# DashHubV6.net
KiCad netlist of a schematic drawn in EAGLE
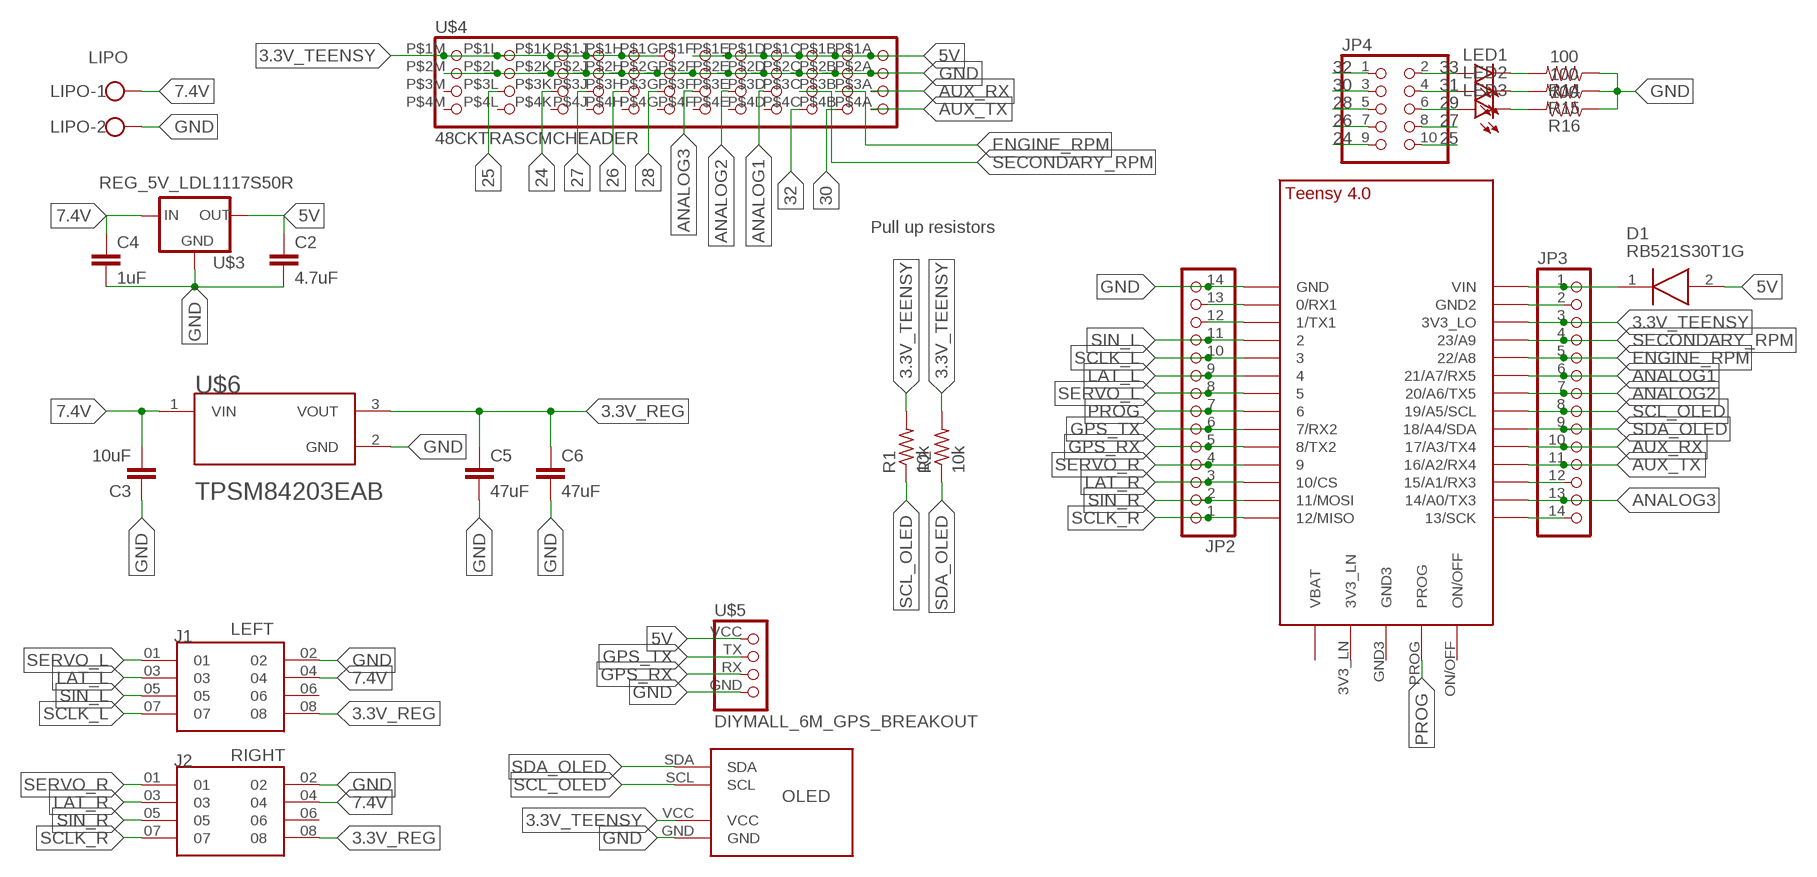
[diagram p0: schematic, sheet 1]

(export (version "E")
  (design (tool "Eeschema 10.0.6"))
  (components
    (comp (ref "C2")
      (value "4.7uF")
      (footprint "eagle-import:C0603")
      (libsource (lib "eagle-import") (part "CAP_SMDC0603"))
    )
    (comp (ref "C3")
      (value "10uF")
      (footprint "eagle-import:C1206")
      (libsource (lib "eagle-import") (part "CAP_SMDC1206"))
    )
    (comp (ref "C4")
      (value "1uF")
      (footprint "eagle-import:C1206")
      (libsource (lib "eagle-import") (part "CAP_SMDC1206"))
    )
    (comp (ref "C5")
      (value "47uF")
      (footprint "eagle-import:C1206")
      (libsource (lib "eagle-import") (part "CAP_SMDC1206"))
    )
    (comp (ref "C6")
      (value "47uF")
      (footprint "eagle-import:C1206")
      (libsource (lib "eagle-import") (part "CAP_SMDC1206"))
    )
    (comp (ref "D1")
      (value "RB521S30T1G")
      (footprint "eagle-import:SODFL1608X70N")
      (fields (field (name "MOUSER_PART_NUMBER") "863-RB521S30T1G"))
      (libsource (lib "eagle-import") (part "RB521S30T1G"))
    )
    (comp (ref "J1")
      (value "LEFT")
      (footprint "eagle-import:SAMTEC_ESW-104-23-L-D")
      (fields (field (name "MANUFACTURER") "Samtec Inc."))
      (libsource (lib "eagle-import") (part "ESW-104-23-L-D"))
    )
    (comp (ref "J2")
      (value "RIGHT")
      (footprint "eagle-import:SAMTEC_ESW-104-23-L-D")
      (fields (field (name "MANUFACTURER") "Samtec Inc."))
      (libsource (lib "eagle-import") (part "ESW-104-23-L-D"))
    )
    (comp (ref "JP2")
      (value "PINHD-1X14")
      (footprint "eagle-import:1X14")
      (libsource (lib "eagle-import") (part "PINHD-1X14"))
    )
    (comp (ref "JP3")
      (value "PINHD-1X14")
      (footprint "eagle-import:1X14")
      (libsource (lib "eagle-import") (part "PINHD-1X14"))
    )
    (comp (ref "JP4")
      (value "PINHD-2X5")
      (footprint "eagle-import:2X05")
      (libsource (lib "eagle-import") (part "PINHD-2X5"))
    )
    (comp (ref "LED1")
      (value "LEDCHIPLED_1206")
      (footprint "eagle-import:CHIPLED_1206")
      (libsource (lib "eagle-import") (part "LEDCHIPLED_1206"))
    )
    (comp (ref "LED2")
      (value "LEDCHIPLED_1206")
      (footprint "eagle-import:CHIPLED_1206")
      (libsource (lib "eagle-import") (part "LEDCHIPLED_1206"))
    )
    (comp (ref "LED3")
      (value "LEDCHIPLED_1206")
      (footprint "eagle-import:CHIPLED_1206")
      (libsource (lib "eagle-import") (part "LEDCHIPLED_1206"))
    )
    (comp (ref "LIPO")
      (value "LIPO")
      (footprint "eagle-import:W237-102")
      (fields (field (name "MPN") "237-102"))
      (libsource (lib "eagle-import") (part "W237-102"))
    )
    (comp (ref "R1")
      (value "10k")
      (footprint "eagle-import:R0603")
      (libsource (lib "eagle-import") (part "RES_SMDR0603"))
    )
    (comp (ref "R2")
      (value "10k")
      (footprint "eagle-import:R0603")
      (libsource (lib "eagle-import") (part "RES_SMDR0603"))
    )
    (comp (ref "R14")
      (value "100")
      (footprint "eagle-import:AXIAL-0.3")
      (libsource (lib "eagle-import") (part "RESISTORAXIAL-0.3"))
    )
    (comp (ref "R15")
      (value "100")
      (footprint "eagle-import:AXIAL-0.3")
      (libsource (lib "eagle-import") (part "RESISTORAXIAL-0.3"))
    )
    (comp (ref "R16")
      (value "100")
      (footprint "eagle-import:AXIAL-0.3")
      (libsource (lib "eagle-import") (part "RESISTORAXIAL-0.3"))
    )
    (comp (ref "U$1")
      (value "TEENSY_4.0-BASIC")
      (footprint "eagle-import:TEENSY_4.0-BASIC")
      (libsource (lib "eagle-import") (part "TEENSY_4.0-BASIC"))
    )
    (comp (ref "U$2")
      (value "OLED_SSD1306")
      (footprint "eagle-import:OLED_SSD1306")
      (libsource (lib "eagle-import") (part "OLED_SSD1306"))
    )
    (comp (ref "U$3")
      (value "REG_5V_LDL1117S50R")
      (footprint "eagle-import:SOT230P700X180-4N")
      (libsource (lib "eagle-import") (part "REG_5V_LDL1117S50R"))
    )
    (comp (ref "U$4")
      (value "48CKTRASCMCHEADER")
      (footprint "eagle-import:48CKTRASCMCHEADER")
      (libsource (lib "eagle-import") (part "48CKTRASCMCHEADER"))
    )
    (comp (ref "U$5")
      (value "DIYMALL_6M_GPS_BREAKOUT")
      (footprint "eagle-import:DIYMALL_6M_GPS_BREAKOUT")
      (libsource (lib "eagle-import") (part "DIYMALL_6M_GPS_BREAKOUT"))
    )
    (comp (ref "U$6")
      (value "TPSM84205EAB")
      (footprint "eagle-import:TPSM84205EAB")
      (libsource (lib "eagle-import") (part "TPSM84205EAB"))
    )
  )
  (nets
    (net (code "1") (name "/29") (class "Default")
      (node (ref "JP4") (pin "6") (pinfunction "6_6") (pintype "passive"))
      (node (ref "LED3") (pin "A") (pinfunction "A_A") (pintype "passive"))
    )
    (net (code "2") (name "/31") (class "Default")
      (node (ref "JP4") (pin "4") (pinfunction "4_4") (pintype "passive"))
      (node (ref "LED2") (pin "A") (pinfunction "A_A") (pintype "passive"))
    )
    (net (code "3") (name "/33") (class "Default")
      (node (ref "JP4") (pin "2") (pinfunction "2_2") (pintype "passive"))
      (node (ref "LED1") (pin "A") (pinfunction "A_A") (pintype "passive"))
    )
    (net (code "4") (name "3.3V_REG") (class "Default")
      (node (ref "C5") (pin "1") (pinfunction "1_1") (pintype "passive"))
      (node (ref "C6") (pin "1") (pinfunction "1_1") (pintype "passive"))
      (node (ref "J1") (pin "08") (pinfunction "08_08") (pintype "passive"))
      (node (ref "J2") (pin "08") (pinfunction "08_08") (pintype "passive"))
      (node (ref "U$6") (pin "3") (pinfunction "VOUT_3") (pintype "power_in"))
    )
    (net (code "5") (name "3.3V_TEENSY") (class "Default")
      (node (ref "JP3") (pin "3") (pinfunction "3_3") (pintype "passive"))
      (node (ref "R1") (pin "2") (pinfunction "2_2") (pintype "passive"))
      (node (ref "R2") (pin "2") (pinfunction "2_2") (pintype "passive"))
      (node (ref "U$1") (pin "3V3_LO") (pinfunction "3V3_LO_3V3_LO") (pintype "bidirectional"))
      (node (ref "U$2") (pin "VCC") (pinfunction "VCC_VCC") (pintype "bidirectional"))
      (node (ref "U$4") (pin "P$1G") (pinfunction "1G_P$1G") (pintype "passive"))
      (node (ref "U$4") (pin "P$1H") (pinfunction "1H_P$1H") (pintype "passive"))
      (node (ref "U$4") (pin "P$1J") (pinfunction "1J_P$1J") (pintype "passive"))
      (node (ref "U$4") (pin "P$1K") (pinfunction "1K_P$1K") (pintype "passive"))
      (node (ref "U$4") (pin "P$1L") (pinfunction "1L_P$1L") (pintype "passive"))
      (node (ref "U$4") (pin "P$1M") (pinfunction "1M_P$1M") (pintype "passive"))
    )
    (net (code "6") (name "5V") (class "Default")
      (node (ref "C2") (pin "1") (pinfunction "1_1") (pintype "passive"))
      (node (ref "D1") (pin "2") (pinfunction "A_2") (pintype "bidirectional"))
      (node (ref "U$3") (pin "2") (pinfunction "OUT_2") (pintype "output"))
      (node (ref "U$3") (pin "4") (pinfunction "OUT_4") (pintype "output"))
      (node (ref "U$4") (pin "P$1A") (pinfunction "1A_P$1A") (pintype "passive"))
      (node (ref "U$4") (pin "P$1B") (pinfunction "1B_P$1B") (pintype "passive"))
      (node (ref "U$4") (pin "P$1C") (pinfunction "1C_P$1C") (pintype "passive"))
      (node (ref "U$4") (pin "P$1D") (pinfunction "1D_P$1D") (pintype "passive"))
      (node (ref "U$4") (pin "P$1E") (pinfunction "1E_P$1E") (pintype "passive"))
      (node (ref "U$4") (pin "P$1F") (pinfunction "1F_P$1F") (pintype "passive"))
      (node (ref "U$5") (pin "VCC") (pinfunction "VCC_VCC") (pintype "passive"))
    )
    (net (code "7") (name "7.4V") (class "Default")
      (node (ref "C3") (pin "2") (pinfunction "2_2") (pintype "passive"))
      (node (ref "C4") (pin "1") (pinfunction "1_1") (pintype "passive"))
      (node (ref "J1") (pin "04") (pinfunction "04_04") (pintype "passive"))
      (node (ref "J2") (pin "04") (pinfunction "04_04") (pintype "passive"))
      (node (ref "LIPO") (pin "1") (pinfunction "KL_1") (pintype "passive"))
      (node (ref "U$3") (pin "3") (pinfunction "IN_3") (pintype "input"))
      (node (ref "U$6") (pin "1") (pinfunction "VIN_1") (pintype "power_in"))
    )
    (net (code "8") (name "24") (class "Default")
      (node (ref "JP4") (pin "9") (pinfunction "9_9") (pintype "passive"))
      (node (ref "U$4") (pin "P$3K") (pinfunction "3K_P$3K") (pintype "passive"))
    )
    (net (code "9") (name "25") (class "Default")
      (node (ref "JP4") (pin "10") (pinfunction "10_10") (pintype "passive"))
      (node (ref "U$4") (pin "P$3L") (pinfunction "3L_P$3L") (pintype "passive"))
    )
    (net (code "10") (name "26") (class "Default")
      (node (ref "JP4") (pin "7") (pinfunction "7_7") (pintype "passive"))
      (node (ref "U$4") (pin "P$3H") (pinfunction "3H_P$3H") (pintype "passive"))
    )
    (net (code "11") (name "27") (class "Default")
      (node (ref "JP4") (pin "8") (pinfunction "8_8") (pintype "passive"))
      (node (ref "U$4") (pin "P$3J") (pinfunction "3J_P$3J") (pintype "passive"))
    )
    (net (code "12") (name "28") (class "Default")
      (node (ref "JP4") (pin "5") (pinfunction "5_5") (pintype "passive"))
      (node (ref "U$4") (pin "P$3G") (pinfunction "3G_P$3G") (pintype "passive"))
    )
    (net (code "13") (name "30") (class "Default")
      (node (ref "JP4") (pin "3") (pinfunction "3_3") (pintype "passive"))
      (node (ref "U$4") (pin "P$4B") (pinfunction "4B_P$4B") (pintype "passive"))
    )
    (net (code "14") (name "32") (class "Default")
      (node (ref "JP4") (pin "1") (pinfunction "1_1") (pintype "passive"))
      (node (ref "U$4") (pin "P$4C") (pinfunction "4C_P$4C") (pintype "passive"))
    )
    (net (code "15") (name "ANALOG1") (class "Default")
      (node (ref "JP3") (pin "6") (pinfunction "6_6") (pintype "passive"))
      (node (ref "U$1") (pin "21/A7") (pinfunction "21/A7/RX5_21/A7") (pintype "bidirectional"))
      (node (ref "U$4") (pin "P$3D") (pinfunction "3D_P$3D") (pintype "passive"))
    )
    (net (code "16") (name "ANALOG2") (class "Default")
      (node (ref "JP3") (pin "7") (pinfunction "7_7") (pintype "passive"))
      (node (ref "U$1") (pin "20/A6") (pinfunction "20/A6/TX5_20/A6") (pintype "bidirectional"))
      (node (ref "U$4") (pin "P$3E") (pinfunction "3E_P$3E") (pintype "passive"))
    )
    (net (code "17") (name "ANALOG3") (class "Default")
      (node (ref "JP3") (pin "13") (pinfunction "13_13") (pintype "passive"))
      (node (ref "U$1") (pin "14/A0") (pinfunction "14/A0/TX3_14/A0") (pintype "bidirectional"))
      (node (ref "U$4") (pin "P$3F") (pinfunction "3F_P$3F") (pintype "passive"))
    )
    (net (code "18") (name "AUX_RX") (class "Default")
      (node (ref "JP3") (pin "10") (pinfunction "10_10") (pintype "passive"))
      (node (ref "U$1") (pin "17/A3") (pinfunction "17/A3/TX4_17/A3") (pintype "bidirectional"))
      (node (ref "U$4") (pin "P$3A") (pinfunction "3A_P$3A") (pintype "passive"))
    )
    (net (code "19") (name "AUX_TX") (class "Default")
      (node (ref "JP3") (pin "11") (pinfunction "11_11") (pintype "passive"))
      (node (ref "U$1") (pin "16/A2") (pinfunction "16/A2/RX4_16/A2") (pintype "bidirectional"))
      (node (ref "U$4") (pin "P$4A") (pinfunction "4A_P$4A") (pintype "passive"))
    )
    (net (code "20") (name "ENGINE_RPM") (class "Default")
      (node (ref "JP3") (pin "5") (pinfunction "5_5") (pintype "passive"))
      (node (ref "U$1") (pin "22/A8") (pinfunction "22/A8_22/A8") (pintype "bidirectional"))
      (node (ref "U$4") (pin "P$3B") (pinfunction "3B_P$3B") (pintype "passive"))
    )
    (net (code "21") (name "GND") (class "Default")
      (node (ref "C2") (pin "2") (pinfunction "2_2") (pintype "passive"))
      (node (ref "C3") (pin "1") (pinfunction "1_1") (pintype "passive"))
      (node (ref "C4") (pin "2") (pinfunction "2_2") (pintype "passive"))
      (node (ref "C5") (pin "2") (pinfunction "2_2") (pintype "passive"))
      (node (ref "C6") (pin "2") (pinfunction "2_2") (pintype "passive"))
      (node (ref "J1") (pin "02") (pinfunction "02_02") (pintype "passive"))
      (node (ref "J2") (pin "02") (pinfunction "02_02") (pintype "passive"))
      (node (ref "JP2") (pin "14") (pinfunction "14_14") (pintype "passive"))
      (node (ref "LIPO") (pin "2") (pinfunction "KL_2") (pintype "passive"))
      (node (ref "R14") (pin "P$1") (pinfunction "1_P$1") (pintype "passive"))
      (node (ref "R15") (pin "P$1") (pinfunction "1_P$1") (pintype "passive"))
      (node (ref "R16") (pin "P$1") (pinfunction "1_P$1") (pintype "passive"))
      (node (ref "U$1") (pin "GND") (pinfunction "GND_GND") (pintype "bidirectional"))
      (node (ref "U$2") (pin "GND") (pinfunction "GND_GND") (pintype "bidirectional"))
      (node (ref "U$3") (pin "1") (pinfunction "GND_1") (pintype "input"))
      (node (ref "U$4") (pin "P$2A") (pinfunction "2A_P$2A") (pintype "passive"))
      (node (ref "U$4") (pin "P$2B") (pinfunction "2B_P$2B") (pintype "passive"))
      (node (ref "U$4") (pin "P$2C") (pinfunction "2C_P$2C") (pintype "passive"))
      (node (ref "U$4") (pin "P$2D") (pinfunction "2D_P$2D") (pintype "passive"))
      (node (ref "U$4") (pin "P$2E") (pinfunction "2E_P$2E") (pintype "passive"))
      (node (ref "U$4") (pin "P$2F") (pinfunction "2F_P$2F") (pintype "passive"))
      (node (ref "U$4") (pin "P$2G") (pinfunction "2G_P$2G") (pintype "passive"))
      (node (ref "U$4") (pin "P$2H") (pinfunction "2H_P$2H") (pintype "passive"))
      (node (ref "U$4") (pin "P$2J") (pinfunction "2J_P$2J") (pintype "passive"))
      (node (ref "U$4") (pin "P$2K") (pinfunction "2K_P$2K") (pintype "passive"))
      (node (ref "U$4") (pin "P$2L") (pinfunction "2L_P$2L") (pintype "passive"))
      (node (ref "U$4") (pin "P$2M") (pinfunction "2M_P$2M") (pintype "passive"))
      (node (ref "U$5") (pin "GND") (pinfunction "GND_GND") (pintype "passive"))
      (node (ref "U$6") (pin "2") (pinfunction "GND_2") (pintype "power_in"))
    )
    (net (code "22") (name "GPS_RX") (class "Default")
      (node (ref "JP2") (pin "5") (pinfunction "5_5") (pintype "passive"))
      (node (ref "U$1") (pin "8") (pinfunction "8/TX2_8") (pintype "bidirectional"))
      (node (ref "U$5") (pin "RX") (pinfunction "RX_RX") (pintype "passive"))
    )
    (net (code "23") (name "GPS_TX") (class "Default")
      (node (ref "JP2") (pin "6") (pinfunction "6_6") (pintype "passive"))
      (node (ref "U$1") (pin "7") (pinfunction "7/RX2_7") (pintype "bidirectional"))
      (node (ref "U$5") (pin "TX") (pinfunction "TX_TX") (pintype "passive"))
    )
    (net (code "24") (name "LAT_L") (class "Default")
      (node (ref "J1") (pin "03") (pinfunction "03_03") (pintype "passive"))
      (node (ref "JP2") (pin "9") (pinfunction "9_9") (pintype "passive"))
      (node (ref "U$1") (pin "4/CANRX") (pinfunction "4_4/CANRX") (pintype "bidirectional"))
    )
    (net (code "25") (name "LAT_R") (class "Default")
      (node (ref "J2") (pin "03") (pinfunction "03_03") (pintype "passive"))
      (node (ref "JP2") (pin "3") (pinfunction "3_3") (pintype "passive"))
      (node (ref "U$1") (pin "10/CS") (pinfunction "10/CS_10/CS") (pintype "bidirectional"))
    )
    (net (code "26") (name "Net-(D1-K)") (class "Default")
      (node (ref "D1") (pin "1") (pinfunction "K_1") (pintype "bidirectional"))
      (node (ref "JP3") (pin "1") (pinfunction "1_1") (pintype "passive"))
      (node (ref "U$1") (pin "VIN") (pinfunction "VIN_VIN") (pintype "bidirectional"))
    )
    (net (code "27") (name "Net-(JP3-Pad2)") (class "Default")
      (node (ref "JP3") (pin "2") (pinfunction "2_2") (pintype "passive"))
      (node (ref "U$1") (pin "GND2") (pinfunction "GND2_GND2") (pintype "bidirectional"))
    )
    (net (code "28") (name "Net-(JP3-Pad14)") (class "Default")
      (node (ref "JP3") (pin "14") (pinfunction "14_14") (pintype "passive"))
      (node (ref "U$1") (pin "13/SCK") (pinfunction "13/SCK_13/SCK") (pintype "bidirectional"))
    )
    (net (code "29") (name "Net-(R14-2)") (class "Default")
      (node (ref "LED1") (pin "C") (pinfunction "C_C") (pintype "passive"))
      (node (ref "R14") (pin "P$2") (pinfunction "2_P$2") (pintype "passive"))
    )
    (net (code "30") (name "Net-(R15-2)") (class "Default")
      (node (ref "LED2") (pin "C") (pinfunction "C_C") (pintype "passive"))
      (node (ref "R15") (pin "P$2") (pinfunction "2_P$2") (pintype "passive"))
    )
    (net (code "31") (name "Net-(R16-2)") (class "Default")
      (node (ref "LED3") (pin "C") (pinfunction "C_C") (pintype "passive"))
      (node (ref "R16") (pin "P$2") (pinfunction "2_P$2") (pintype "passive"))
    )
    (net (code "32") (name "Net-(U$1-0{slash}RX1)") (class "Default")
      (node (ref "JP2") (pin "13") (pinfunction "13_13") (pintype "passive"))
      (node (ref "U$1") (pin "0/RX") (pinfunction "0/RX1_0/RX") (pintype "bidirectional"))
    )
    (net (code "33") (name "Net-(U$1-1{slash}TX1)") (class "Default")
      (node (ref "JP2") (pin "12") (pinfunction "12_12") (pintype "passive"))
      (node (ref "U$1") (pin "1/TX") (pinfunction "1/TX1_1/TX") (pintype "bidirectional"))
    )
    (net (code "34") (name "Net-(U$1-15{slash}A1{slash}RX3)") (class "Default")
      (node (ref "JP3") (pin "12") (pinfunction "12_12") (pintype "passive"))
      (node (ref "U$1") (pin "15/A1") (pinfunction "15/A1/RX3_15/A1") (pintype "bidirectional"))
    )
    (net (code "35") (name "PROG") (class "Default")
      (node (ref "JP2") (pin "7") (pinfunction "7_7") (pintype "passive"))
      (node (ref "U$1") (pin "6") (pinfunction "6_6") (pintype "bidirectional"))
      (node (ref "U$1") (pin "PROG") (pinfunction "PROG_PROG") (pintype "bidirectional"))
    )
    (net (code "36") (name "SCLK_L") (class "Default")
      (node (ref "J1") (pin "07") (pinfunction "07_07") (pintype "passive"))
      (node (ref "JP2") (pin "10") (pinfunction "10_10") (pintype "passive"))
      (node (ref "U$1") (pin "3/CANTX") (pinfunction "3_3/CANTX") (pintype "bidirectional"))
    )
    (net (code "37") (name "SCLK_R") (class "Default")
      (node (ref "J2") (pin "07") (pinfunction "07_07") (pintype "passive"))
      (node (ref "JP2") (pin "1") (pinfunction "1_1") (pintype "passive"))
      (node (ref "U$1") (pin "12/MISO") (pinfunction "12/MISO_12/MISO") (pintype "bidirectional"))
    )
    (net (code "38") (name "SCL_OLED") (class "Default")
      (node (ref "JP3") (pin "8") (pinfunction "8_8") (pintype "passive"))
      (node (ref "R1") (pin "1") (pinfunction "1_1") (pintype "passive"))
      (node (ref "U$1") (pin "19/A5/SCL") (pinfunction "19/A5/SCL_19/A5/SCL") (pintype "bidirectional"))
      (node (ref "U$2") (pin "SCL") (pinfunction "SCL_SCL") (pintype "bidirectional"))
    )
    (net (code "39") (name "SDA_OLED") (class "Default")
      (node (ref "JP3") (pin "9") (pinfunction "9_9") (pintype "passive"))
      (node (ref "R2") (pin "1") (pinfunction "1_1") (pintype "passive"))
      (node (ref "U$1") (pin "18/A4/SDA") (pinfunction "18/A4/SDA_18/A4/SDA") (pintype "bidirectional"))
      (node (ref "U$2") (pin "SDA") (pinfunction "SDA_SDA") (pintype "bidirectional"))
    )
    (net (code "40") (name "SECONDARY_RPM") (class "Default")
      (node (ref "JP3") (pin "4") (pinfunction "4_4") (pintype "passive"))
      (node (ref "U$1") (pin "23/A9") (pinfunction "23/A9_23/A9") (pintype "bidirectional"))
      (node (ref "U$4") (pin "P$3C") (pinfunction "3C_P$3C") (pintype "passive"))
    )
    (net (code "41") (name "SERVO_L") (class "Default")
      (node (ref "J1") (pin "01") (pinfunction "01_01") (pintype "passive"))
      (node (ref "JP2") (pin "8") (pinfunction "8_8") (pintype "passive"))
      (node (ref "U$1") (pin "5") (pinfunction "5_5") (pintype "bidirectional"))
    )
    (net (code "42") (name "SERVO_R") (class "Default")
      (node (ref "J2") (pin "01") (pinfunction "01_01") (pintype "passive"))
      (node (ref "JP2") (pin "4") (pinfunction "4_4") (pintype "passive"))
      (node (ref "U$1") (pin "9/CS") (pinfunction "9_9/CS") (pintype "bidirectional"))
    )
    (net (code "43") (name "SIN_L") (class "Default")
      (node (ref "J1") (pin "05") (pinfunction "05_05") (pintype "passive"))
      (node (ref "JP2") (pin "11") (pinfunction "11_11") (pintype "passive"))
      (node (ref "U$1") (pin "2") (pinfunction "2_2") (pintype "bidirectional"))
    )
    (net (code "44") (name "SIN_R") (class "Default")
      (node (ref "J2") (pin "05") (pinfunction "05_05") (pintype "passive"))
      (node (ref "JP2") (pin "2") (pinfunction "2_2") (pintype "passive"))
      (node (ref "U$1") (pin "11/MOSI") (pinfunction "11/MOSI_11/MOSI") (pintype "bidirectional"))
    )
    (net (code "45") (name "unconnected-(J1-Pad06)") (class "Default")
      (node (ref "J1") (pin "06") (pinfunction "06_06") (pintype "passive"))
    )
    (net (code "46") (name "unconnected-(J2-Pad06)") (class "Default")
      (node (ref "J2") (pin "06") (pinfunction "06_06") (pintype "passive"))
    )
    (net (code "47") (name "unconnected-(U$1-Pad3V3_LN)") (class "Default")
      (node (ref "U$1") (pin "3V3_LN") (pinfunction "3V3_LN_3V3_LN") (pintype "bidirectional"))
    )
    (net (code "48") (name "unconnected-(U$1-PadGND3)") (class "Default")
      (node (ref "U$1") (pin "GND3") (pinfunction "GND3_GND3") (pintype "bidirectional"))
    )
    (net (code "49") (name "unconnected-(U$1-PadON{slash}OFF)") (class "Default")
      (node (ref "U$1") (pin "ON/OFF") (pinfunction "ON/OFF_ON/OFF") (pintype "bidirectional"))
    )
    (net (code "50") (name "unconnected-(U$1-VBAT-PadVBAT\\)") (class "Default")
      (node (ref "U$1") (pin "VBAT\\") (pinfunction "VBAT_VBAT\\") (pintype "bidirectional"))
    )
    (net (code "51") (name "unconnected-(U$4-3M-PadP$3M)") (class "Default")
      (node (ref "U$4") (pin "P$3M") (pinfunction "3M_P$3M") (pintype "passive"))
    )
    (net (code "52") (name "unconnected-(U$4-4D-PadP$4D)") (class "Default")
      (node (ref "U$4") (pin "P$4D") (pinfunction "4D_P$4D") (pintype "passive"))
    )
    (net (code "53") (name "unconnected-(U$4-4E-PadP$4E)") (class "Default")
      (node (ref "U$4") (pin "P$4E") (pinfunction "4E_P$4E") (pintype "passive"))
    )
    (net (code "54") (name "unconnected-(U$4-4F-PadP$4F)") (class "Default")
      (node (ref "U$4") (pin "P$4F") (pinfunction "4F_P$4F") (pintype "passive"))
    )
    (net (code "55") (name "unconnected-(U$4-4G-PadP$4G)") (class "Default")
      (node (ref "U$4") (pin "P$4G") (pinfunction "4G_P$4G") (pintype "passive"))
    )
    (net (code "56") (name "unconnected-(U$4-4H-PadP$4H)") (class "Default")
      (node (ref "U$4") (pin "P$4H") (pinfunction "4H_P$4H") (pintype "passive"))
    )
    (net (code "57") (name "unconnected-(U$4-4J-PadP$4J)") (class "Default")
      (node (ref "U$4") (pin "P$4J") (pinfunction "4J_P$4J") (pintype "passive"))
    )
    (net (code "58") (name "unconnected-(U$4-4K-PadP$4K)") (class "Default")
      (node (ref "U$4") (pin "P$4K") (pinfunction "4K_P$4K") (pintype "passive"))
    )
    (net (code "59") (name "unconnected-(U$4-4L-PadP$4L)") (class "Default")
      (node (ref "U$4") (pin "P$4L") (pinfunction "4L_P$4L") (pintype "passive"))
    )
    (net (code "60") (name "unconnected-(U$4-4M-PadP$4M)") (class "Default")
      (node (ref "U$4") (pin "P$4M") (pinfunction "4M_P$4M") (pintype "passive"))
    )
  )
)
